# controller.net
KiCad netlist of a schematic drawn in Altium Designer
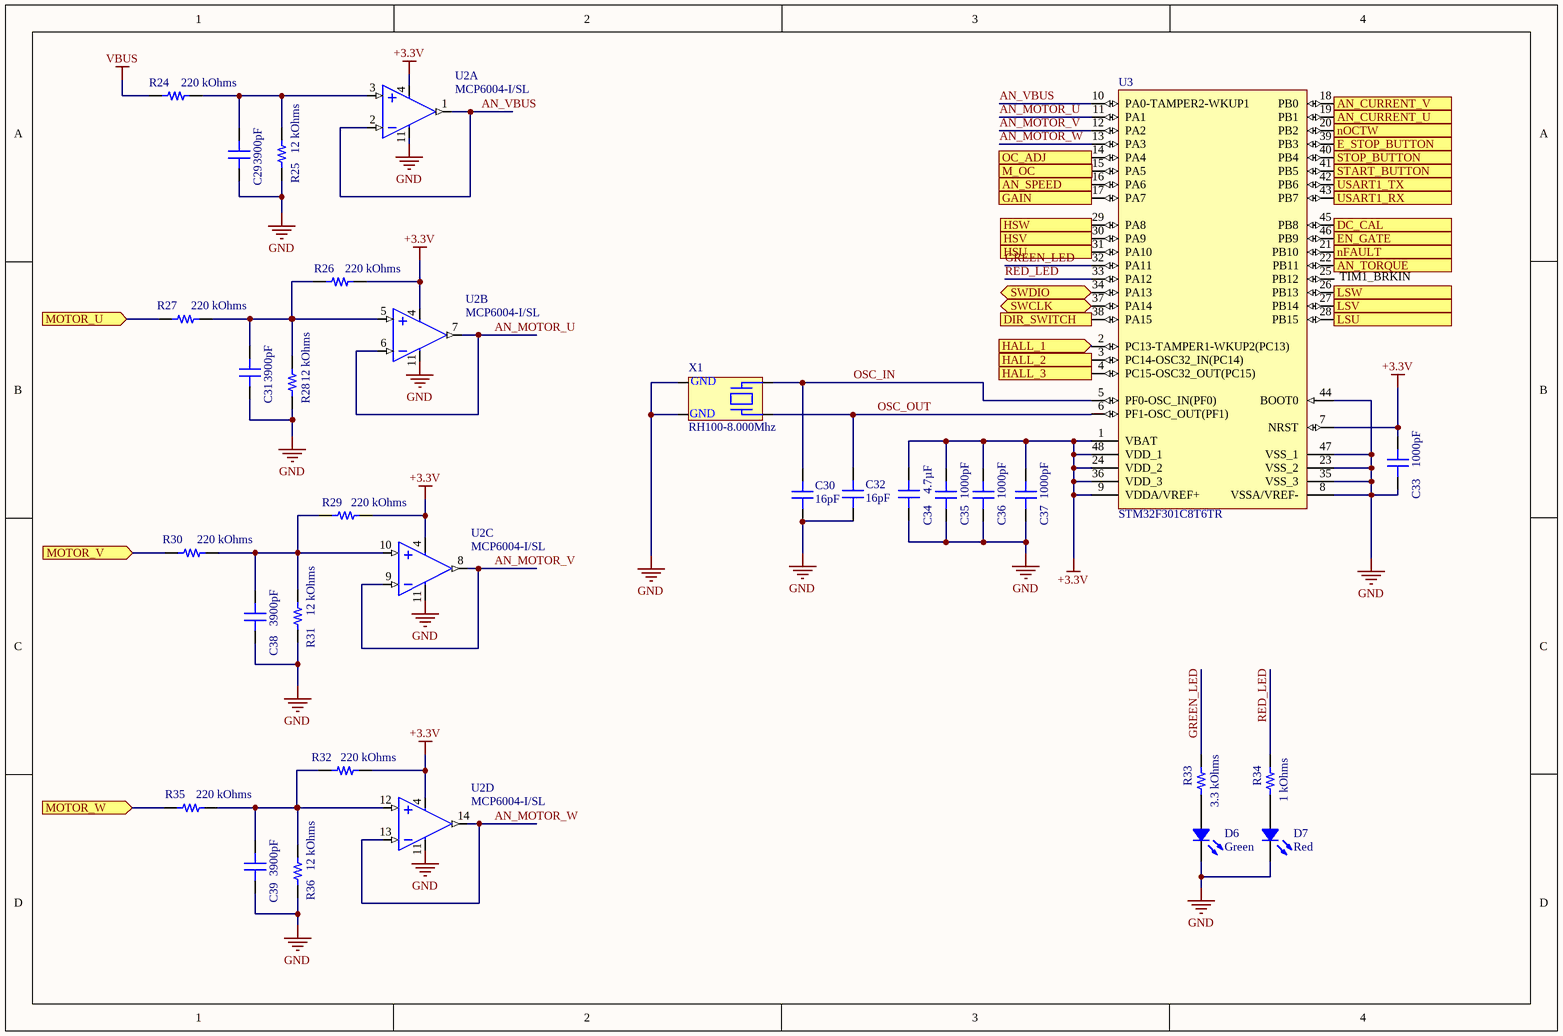
[diagram p0: controller.SchDoc]

(export (version "E")
  (design (tool "Eeschema 10.0.6"))
  (components
    (comp (ref "C29")
      (value "3900pF")
      (footprint "CAP 0402_1005")
      (description "CAP CER 3900PF 50V X7R 0402")
      (fields (field (name "PART NUMBER") "CC0402JRX7R9BB392") (field (name "MANUFACTURER") "Yageo"))
      (libsource (lib "Celestial Altium Library - altium_library") (part "Capacitor"))
    )
    (comp (ref "C30")
      (value "16pF")
      (footprint "CAP 0402_1005")
      (description "CAP CER 16PF 50V C0G/NP0 0402")
      (fields (field (name "PART NUMBER") "CBR04C160F5GAC") (field (name "MANUFACTURER") "KEMET"))
      (libsource (lib "Celestial Altium Library - altium_library") (part "Capacitor"))
    )
    (comp (ref "C31")
      (value "3900pF")
      (footprint "CAP 0402_1005")
      (description "CAP CER 3900PF 50V X7R 0402")
      (fields (field (name "PART NUMBER") "CC0402JRX7R9BB392") (field (name "MANUFACTURER") "Yageo"))
      (libsource (lib "Celestial Altium Library - altium_library") (part "Capacitor"))
    )
    (comp (ref "C32")
      (value "16pF")
      (footprint "CAP 0402_1005")
      (description "CAP CER 16PF 50V C0G/NP0 0402")
      (fields (field (name "PART NUMBER") "CBR04C160F5GAC") (field (name "MANUFACTURER") "KEMET"))
      (libsource (lib "Celestial Altium Library - altium_library") (part "Capacitor"))
    )
    (comp (ref "C33")
      (value "1000pF")
      (footprint "CAP 0402_1005")
      (description "CAP CER 1000PF 25V X7R 0402")
      (fields
        (field (name "PART NUMBER") "CGJ2B2X7R1E102K050BA")
        (field (name "MANUFACTURER") "TDK Corporation")
      )
      (libsource (lib "Celestial Altium Library - altium_library") (part "Capacitor"))
    )
    (comp (ref "C34")
      (value "4.7µF")
      (footprint "CAP 1206_3216 - 1.0MM")
      (description "CAP CER 4.7UF 25V X7R 1206")
      (fields
        (field (name "PART NUMBER") "C3216X7R1E475K085AB")
        (field (name "MANUFACTURER") "TDK Corporation")
      )
      (libsource (lib "Celestial Altium Library - altium_library") (part "Capacitor"))
    )
    (comp (ref "C35")
      (value "1000pF")
      (footprint "CAP 0402_1005")
      (description "CAP CER 1000PF 25V X7R 0402")
      (fields
        (field (name "PART NUMBER") "CGJ2B2X7R1E102K050BA")
        (field (name "MANUFACTURER") "TDK Corporation")
      )
      (libsource (lib "Celestial Altium Library - altium_library") (part "Capacitor"))
    )
    (comp (ref "C36")
      (value "1000pF")
      (footprint "CAP 0402_1005")
      (description "CAP CER 1000PF 25V X7R 0402")
      (fields
        (field (name "PART NUMBER") "CGJ2B2X7R1E102K050BA")
        (field (name "MANUFACTURER") "TDK Corporation")
      )
      (libsource (lib "Celestial Altium Library - altium_library") (part "Capacitor"))
    )
    (comp (ref "C37")
      (value "1000pF")
      (footprint "CAP 0402_1005")
      (description "CAP CER 1000PF 25V X7R 0402")
      (fields
        (field (name "PART NUMBER") "CGJ2B2X7R1E102K050BA")
        (field (name "MANUFACTURER") "TDK Corporation")
      )
      (libsource (lib "Celestial Altium Library - altium_library") (part "Capacitor"))
    )
    (comp (ref "C38")
      (value "3900pF")
      (footprint "CAP 0402_1005")
      (description "CAP CER 3900PF 50V X7R 0402")
      (fields (field (name "PART NUMBER") "CC0402JRX7R9BB392") (field (name "MANUFACTURER") "Yageo"))
      (libsource (lib "Celestial Altium Library - altium_library") (part "Capacitor"))
    )
    (comp (ref "C39")
      (value "3900pF")
      (footprint "CAP 0402_1005")
      (description "CAP CER 3900PF 50V X7R 0402")
      (fields (field (name "PART NUMBER") "CC0402JRX7R9BB392") (field (name "MANUFACTURER") "Yageo"))
      (libsource (lib "Celestial Altium Library - altium_library") (part "Capacitor"))
    )
    (comp (ref "D6")
      (value "Green")
      (footprint "LED 1206_3216 GREEN")
      (description "LED GREEN CLEAR 1206 SMD")
      (fields
        (field (name "PART NUMBER") "SML-LX1206SUGC-TR")
        (field (name "MANUFACTURER") "Lumex Opto/Components Inc.")
      )
      (libsource (lib "Celestial Altium Library - altium_library") (part "LED"))
    )
    (comp (ref "D7")
      (value "Red")
      (footprint "LED 1206_3216 RED")
      (description "LED RED CLEAR CHIP SMD")
      (fields (field (name "PART NUMBER") "AP3216SURCK") (field (name "MANUFACTURER") "Kingbright"))
      (libsource (lib "Celestial Altium Library - altium_library") (part "LED"))
    )
    (comp (ref "R24")
      (value "220 kOhms")
      (footprint "RES 1206_3216")
      (description "RES SMD 220K OHM 1% 1/4W 1206")
      (fields (field (name "PART NUMBER") "AC1206FR-07220KL") (field (name "MANUFACTURER") "Yageo"))
      (libsource (lib "Celestial Altium Library - altium_library") (part "Resistor"))
    )
    (comp (ref "R25")
      (value "12 kOhms")
      (footprint "RES 1206_3216")
      (description "RES 12K OHM 1% 1/4W 1206")
      (fields
        (field (name "PART NUMBER") "RMCF1206FT12K0")
        (field (name "MANUFACTURER") "Stackpole Electronics Inc")
      )
      (libsource (lib "Celestial Altium Library - altium_library") (part "Resistor"))
    )
    (comp (ref "R26")
      (value "220 kOhms")
      (footprint "RES 1206_3216")
      (description "RES SMD 220K OHM 1% 1/4W 1206")
      (fields (field (name "PART NUMBER") "AC1206FR-07220KL") (field (name "MANUFACTURER") "Yageo"))
      (libsource (lib "Celestial Altium Library - altium_library") (part "Resistor"))
    )
    (comp (ref "R27")
      (value "220 kOhms")
      (footprint "RES 1206_3216")
      (description "RES SMD 220K OHM 1% 1/4W 1206")
      (fields (field (name "PART NUMBER") "AC1206FR-07220KL") (field (name "MANUFACTURER") "Yageo"))
      (libsource (lib "Celestial Altium Library - altium_library") (part "Resistor"))
    )
    (comp (ref "R28")
      (value "12 kOhms")
      (footprint "RES 1206_3216")
      (description "RES 12K OHM 1% 1/4W 1206")
      (fields
        (field (name "PART NUMBER") "RMCF1206FT12K0")
        (field (name "MANUFACTURER") "Stackpole Electronics Inc")
      )
      (libsource (lib "Celestial Altium Library - altium_library") (part "Resistor"))
    )
    (comp (ref "R29")
      (value "220 kOhms")
      (footprint "RES 1206_3216")
      (description "RES SMD 220K OHM 1% 1/4W 1206")
      (fields (field (name "PART NUMBER") "AC1206FR-07220KL") (field (name "MANUFACTURER") "Yageo"))
      (libsource (lib "Celestial Altium Library - altium_library") (part "Resistor"))
    )
    (comp (ref "R30")
      (value "220 kOhms")
      (footprint "RES 1206_3216")
      (description "RES SMD 220K OHM 1% 1/4W 1206")
      (fields (field (name "PART NUMBER") "AC1206FR-07220KL") (field (name "MANUFACTURER") "Yageo"))
      (libsource (lib "Celestial Altium Library - altium_library") (part "Resistor"))
    )
    (comp (ref "R31")
      (value "12 kOhms")
      (footprint "RES 1206_3216")
      (description "RES 12K OHM 1% 1/4W 1206")
      (fields
        (field (name "PART NUMBER") "RMCF1206FT12K0")
        (field (name "MANUFACTURER") "Stackpole Electronics Inc")
      )
      (libsource (lib "Celestial Altium Library - altium_library") (part "Resistor"))
    )
    (comp (ref "R32")
      (value "220 kOhms")
      (footprint "RES 1206_3216")
      (description "RES SMD 220K OHM 1% 1/4W 1206")
      (fields (field (name "PART NUMBER") "AC1206FR-07220KL") (field (name "MANUFACTURER") "Yageo"))
      (libsource (lib "Celestial Altium Library - altium_library") (part "Resistor"))
    )
    (comp (ref "R33")
      (value "3.3 kOhms")
      (footprint "RES 1206_3216")
      (description "RES SMD 3.3K OHM 1% 1/4W 1206")
      (fields (field (name "PART NUMBER") "CRCW12063K30FKEA") (field (name "MANUFACTURER") "Vishay Dale"))
      (libsource (lib "Celestial Altium Library - altium_library") (part "Resistor"))
    )
    (comp (ref "R34")
      (value "1 kOhms")
      (footprint "RES 1206_3216")
      (description "RES SMD 1K OHM 1% 1/4W 1206")
      (fields (field (name "PART NUMBER") "RC1206FR-071KL") (field (name "MANUFACTURER") "Yageo"))
      (libsource (lib "Celestial Altium Library - altium_library") (part "Resistor"))
    )
    (comp (ref "R35")
      (value "220 kOhms")
      (footprint "RES 1206_3216")
      (description "RES SMD 220K OHM 1% 1/4W 1206")
      (fields (field (name "PART NUMBER") "AC1206FR-07220KL") (field (name "MANUFACTURER") "Yageo"))
      (libsource (lib "Celestial Altium Library - altium_library") (part "Resistor"))
    )
    (comp (ref "R36")
      (value "12 kOhms")
      (footprint "RES 1206_3216")
      (description "RES 12K OHM 1% 1/4W 1206")
      (fields
        (field (name "PART NUMBER") "RMCF1206FT12K0")
        (field (name "MANUFACTURER") "Stackpole Electronics Inc")
      )
      (libsource (lib "Celestial Altium Library - altium_library") (part "Resistor"))
    )
    (comp (ref "U2")
      (value "MCP6004-I/SL")
      (footprint "SOIC-SL14_N")
      (description "1 MHz, Low-Power Operational Amplifier, 14-Pin SOIC, Industrial Temperature")
      (libsource (lib "My_library_OpAmp") (part "MCP6004"))
    )
    (comp (ref "U3")
      (value "STM32F301C8T6TR")
      (footprint "STM-LQFP48_H")
      (libsource (lib "My_Library_MCU") (part "STM32F301C8T6"))
    )
    (comp (ref "X1")
      (value "RH100-8.000Mhz")
      (footprint "RH100-8.000")
      (libsource (lib "My_library_Oscillator") (part "RH100-8.000Mhz"))
    )
  )
  (nets
    (net (code "1") (name "+3.3V") (class "Default")
      (node (ref "C33") (pin "2") (pinfunction "2_2") (pintype "passive"))
      (node (ref "C34") (pin "2") (pinfunction "2_2") (pintype "passive"))
      (node (ref "C35") (pin "2") (pinfunction "2_2") (pintype "passive"))
      (node (ref "C36") (pin "2") (pinfunction "2_2") (pintype "passive"))
      (node (ref "C37") (pin "2") (pinfunction "2_2") (pintype "passive"))
      (node (ref "R26") (pin "1") (pinfunction "1_1") (pintype "passive"))
      (node (ref "R29") (pin "1") (pinfunction "1_1") (pintype "passive"))
      (node (ref "R32") (pin "1") (pinfunction "1_1") (pintype "passive"))
      (node (ref "U2") (pin "4") (pinfunction "VDD_4") (pintype "passive"))
      (node (ref "U3") (pin "1") (pinfunction "VBAT_1") (pintype "power_in"))
      (node (ref "U3") (pin "24") (pinfunction "VDD_2_24") (pintype "power_in"))
      (node (ref "U3") (pin "36") (pinfunction "VDD_3_36") (pintype "power_in"))
      (node (ref "U3") (pin "48") (pinfunction "VDD_1_48") (pintype "power_in"))
      (node (ref "U3") (pin "7") (pinfunction "NRST_7") (pintype "bidirectional"))
      (node (ref "U3") (pin "9") (pinfunction "VDDA/VREF+_9") (pintype "power_in"))
    )
    (net (code "2") (name "/AN_CURRENT_U") (class "Default")
      (node (ref "U3") (pin "19") (pinfunction "PB1_19") (pintype "bidirectional"))
    )
    (net (code "3") (name "/AN_CURRENT_V") (class "Default")
      (node (ref "U3") (pin "18") (pinfunction "PB0_18") (pintype "bidirectional"))
    )
    (net (code "4") (name "/AN_MOTOR_U") (class "Default")
      (node (ref "U2") (pin "6") (pinfunction "VINB-_6") (pintype "input"))
      (node (ref "U2") (pin "7") (pinfunction "VOUTB_7") (pintype "output"))
      (node (ref "U3") (pin "11") (pinfunction "PA1_11") (pintype "bidirectional"))
    )
    (net (code "5") (name "/AN_MOTOR_V") (class "Default")
      (node (ref "U2") (pin "8") (pinfunction "VOUTC_8") (pintype "output"))
      (node (ref "U2") (pin "9") (pinfunction "VINC-_9") (pintype "input"))
      (node (ref "U3") (pin "12") (pinfunction "PA2_12") (pintype "bidirectional"))
    )
    (net (code "6") (name "/AN_MOTOR_W") (class "Default")
      (node (ref "U2") (pin "13") (pinfunction "VIND-_13") (pintype "input"))
      (node (ref "U2") (pin "14") (pinfunction "VOUTD_14") (pintype "output"))
      (node (ref "U3") (pin "13") (pinfunction "PA3_13") (pintype "bidirectional"))
    )
    (net (code "7") (name "/AN_SPEED") (class "Default")
      (node (ref "U3") (pin "16") (pinfunction "PA6_16") (pintype "bidirectional"))
    )
    (net (code "8") (name "/AN_TORQUE") (class "Default")
      (node (ref "U3") (pin "22") (pinfunction "PB11_22") (pintype "bidirectional"))
    )
    (net (code "9") (name "/AN_VBUS") (class "Default")
      (node (ref "U2") (pin "1") (pinfunction "VOUTA_1") (pintype "output"))
      (node (ref "U2") (pin "2") (pinfunction "VINA-_2") (pintype "input"))
      (node (ref "U3") (pin "10") (pinfunction "PA0-TAMPER2-WKUP1_10") (pintype "bidirectional"))
    )
    (net (code "10") (name "/DC_CAL") (class "Default")
      (node (ref "U3") (pin "45") (pinfunction "PB8_45") (pintype "bidirectional"))
    )
    (net (code "11") (name "/DIR_SWITCH") (class "Default")
      (node (ref "U3") (pin "38") (pinfunction "PA15_38") (pintype "bidirectional"))
    )
    (net (code "12") (name "/EN_GATE") (class "Default")
      (node (ref "U3") (pin "46") (pinfunction "PB9_46") (pintype "bidirectional"))
    )
    (net (code "13") (name "/E_STOP_BUTTON") (class "Default")
      (node (ref "U3") (pin "39") (pinfunction "PB3_39") (pintype "bidirectional"))
    )
    (net (code "14") (name "/GAIN") (class "Default")
      (node (ref "U3") (pin "17") (pinfunction "PA7_17") (pintype "bidirectional"))
    )
    (net (code "15") (name "/GREEN_LED") (class "Default")
      (node (ref "R33") (pin "2") (pinfunction "2_2") (pintype "passive"))
      (node (ref "U3") (pin "32") (pinfunction "PA11_32") (pintype "bidirectional"))
    )
    (net (code "16") (name "/HALL_1") (class "Default")
      (node (ref "U3") (pin "2") (pinfunction "PC13-TAMPER1-WKUP2(PC13)_2") (pintype "bidirectional"))
    )
    (net (code "17") (name "/HALL_2") (class "Default")
      (node (ref "U3") (pin "3") (pinfunction "PC14-OSC32_IN(PC14)_3") (pintype "bidirectional"))
    )
    (net (code "18") (name "/HALL_3") (class "Default")
      (node (ref "U3") (pin "4") (pinfunction "PC15-OSC32_OUT(PC15)_4") (pintype "bidirectional"))
    )
    (net (code "19") (name "/HSU") (class "Default")
      (node (ref "U3") (pin "31") (pinfunction "PA10_31") (pintype "bidirectional"))
    )
    (net (code "20") (name "/HSV") (class "Default")
      (node (ref "U3") (pin "30") (pinfunction "PA9_30") (pintype "bidirectional"))
    )
    (net (code "21") (name "/HSW") (class "Default")
      (node (ref "U3") (pin "29") (pinfunction "PA8_29") (pintype "bidirectional"))
    )
    (net (code "22") (name "/LSU") (class "Default")
      (node (ref "U3") (pin "28") (pinfunction "PB15_28") (pintype "bidirectional"))
    )
    (net (code "23") (name "/LSV") (class "Default")
      (node (ref "U3") (pin "27") (pinfunction "PB14_27") (pintype "bidirectional"))
    )
    (net (code "24") (name "/LSW") (class "Default")
      (node (ref "U3") (pin "26") (pinfunction "PB13_26") (pintype "bidirectional"))
    )
    (net (code "25") (name "/MOTOR_U") (class "Default")
      (node (ref "R27") (pin "2") (pinfunction "2_2") (pintype "passive"))
    )
    (net (code "26") (name "/MOTOR_V") (class "Default")
      (node (ref "R30") (pin "2") (pinfunction "2_2") (pintype "passive"))
    )
    (net (code "27") (name "/MOTOR_W") (class "Default")
      (node (ref "R35") (pin "2") (pinfunction "2_2") (pintype "passive"))
    )
    (net (code "28") (name "/M_OC") (class "Default")
      (node (ref "U3") (pin "15") (pinfunction "PA5_15") (pintype "bidirectional"))
    )
    (net (code "29") (name "/OC_ADJ") (class "Default")
      (node (ref "U3") (pin "14") (pinfunction "PA4_14") (pintype "bidirectional"))
    )
    (net (code "30") (name "/OSC_IN") (class "Default")
      (node (ref "C30") (pin "1") (pinfunction "1_1") (pintype "passive"))
      (node (ref "U3") (pin "5") (pinfunction "PF0-OSC_IN(PF0)_5") (pintype "bidirectional"))
      (node (ref "X1") (pin "4") (pinfunction "X1_4") (pintype "passive"))
    )
    (net (code "31") (name "/OSC_OUT") (class "Default")
      (node (ref "C32") (pin "1") (pinfunction "1_1") (pintype "passive"))
      (node (ref "U3") (pin "6") (pinfunction "PF1-OSC_OUT(PF1)_6") (pintype "bidirectional"))
      (node (ref "X1") (pin "2") (pinfunction "X2_2") (pintype "passive"))
    )
    (net (code "32") (name "/RED_LED") (class "Default")
      (node (ref "R34") (pin "2") (pinfunction "2_2") (pintype "passive"))
      (node (ref "U3") (pin "33") (pinfunction "PA12_33") (pintype "bidirectional"))
    )
    (net (code "33") (name "/START_BUTTON") (class "Default")
      (node (ref "U3") (pin "41") (pinfunction "PB5_41") (pintype "bidirectional"))
    )
    (net (code "34") (name "/STOP_BUTTON") (class "Default")
      (node (ref "U3") (pin "40") (pinfunction "PB4_40") (pintype "bidirectional"))
    )
    (net (code "35") (name "/SWCLK") (class "Default")
      (node (ref "U3") (pin "37") (pinfunction "PA14_37") (pintype "bidirectional"))
    )
    (net (code "36") (name "/SWDIO") (class "Default")
      (node (ref "U3") (pin "34") (pinfunction "PA13_34") (pintype "bidirectional"))
    )
    (net (code "37") (name "/USART1_RX") (class "Default")
      (node (ref "U3") (pin "43") (pinfunction "PB7_43") (pintype "bidirectional"))
    )
    (net (code "38") (name "/USART1_TX") (class "Default")
      (node (ref "U3") (pin "42") (pinfunction "PB6_42") (pintype "bidirectional"))
    )
    (net (code "39") (name "/nFAULT") (class "Default")
      (node (ref "U3") (pin "21") (pinfunction "PB10_21") (pintype "bidirectional"))
    )
    (net (code "40") (name "/nOCTW") (class "Default")
      (node (ref "U3") (pin "20") (pinfunction "PB2_20") (pintype "bidirectional"))
    )
    (net (code "41") (name "GND") (class "Default")
      (node (ref "C29") (pin "1") (pinfunction "1_1") (pintype "passive"))
      (node (ref "C30") (pin "2") (pinfunction "2_2") (pintype "passive"))
      (node (ref "C31") (pin "1") (pinfunction "1_1") (pintype "passive"))
      (node (ref "C32") (pin "2") (pinfunction "2_2") (pintype "passive"))
      (node (ref "C33") (pin "1") (pinfunction "1_1") (pintype "passive"))
      (node (ref "C34") (pin "1") (pinfunction "1_1") (pintype "passive"))
      (node (ref "C35") (pin "1") (pinfunction "1_1") (pintype "passive"))
      (node (ref "C36") (pin "1") (pinfunction "1_1") (pintype "passive"))
      (node (ref "C37") (pin "1") (pinfunction "1_1") (pintype "passive"))
      (node (ref "C38") (pin "1") (pinfunction "1_1") (pintype "passive"))
      (node (ref "C39") (pin "1") (pinfunction "1_1") (pintype "passive"))
      (node (ref "D6") (pin "2") (pinfunction "2_2") (pintype "passive"))
      (node (ref "D7") (pin "2") (pinfunction "2_2") (pintype "passive"))
      (node (ref "R25") (pin "1") (pinfunction "1_1") (pintype "passive"))
      (node (ref "R28") (pin "1") (pinfunction "1_1") (pintype "passive"))
      (node (ref "R31") (pin "1") (pinfunction "1_1") (pintype "passive"))
      (node (ref "R36") (pin "1") (pinfunction "1_1") (pintype "passive"))
      (node (ref "U2") (pin "11") (pinfunction "VSS_11") (pintype "power_in"))
      (node (ref "U3") (pin "23") (pinfunction "VSS_2_23") (pintype "power_in"))
      (node (ref "U3") (pin "35") (pinfunction "VSS_3_35") (pintype "power_in"))
      (node (ref "U3") (pin "44") (pinfunction "BOOT0_44") (pintype "input"))
      (node (ref "U3") (pin "47") (pinfunction "VSS_1_47") (pintype "power_in"))
      (node (ref "U3") (pin "8") (pinfunction "VSSA/VREF-_8") (pintype "power_in"))
      (node (ref "X1") (pin "1") (pinfunction "GND_1") (pintype "passive"))
      (node (ref "X1") (pin "3") (pinfunction "GND_3") (pintype "passive"))
    )
    (net (code "42") (name "Net-(D6-Pad1)") (class "Default")
      (node (ref "D6") (pin "1") (pinfunction "1_1") (pintype "passive"))
      (node (ref "R33") (pin "1") (pinfunction "1_1") (pintype "passive"))
    )
    (net (code "43") (name "Net-(D7-Pad1)") (class "Default")
      (node (ref "D7") (pin "1") (pinfunction "1_1") (pintype "passive"))
      (node (ref "R34") (pin "1") (pinfunction "1_1") (pintype "passive"))
    )
    (net (code "44") (name "Net-(U2A-VINA+)") (class "Default")
      (node (ref "C29") (pin "2") (pinfunction "2_2") (pintype "passive"))
      (node (ref "R24") (pin "1") (pinfunction "1_1") (pintype "passive"))
      (node (ref "R25") (pin "2") (pinfunction "2_2") (pintype "passive"))
      (node (ref "U2") (pin "3") (pinfunction "VINA+_3") (pintype "input"))
    )
    (net (code "45") (name "Net-(U2B-VINB+)") (class "Default")
      (node (ref "C31") (pin "2") (pinfunction "2_2") (pintype "passive"))
      (node (ref "R26") (pin "2") (pinfunction "2_2") (pintype "passive"))
      (node (ref "R27") (pin "1") (pinfunction "1_1") (pintype "passive"))
      (node (ref "R28") (pin "2") (pinfunction "2_2") (pintype "passive"))
      (node (ref "U2") (pin "5") (pinfunction "VINB+_5") (pintype "input"))
    )
    (net (code "46") (name "Net-(U2C-VINC+)") (class "Default")
      (node (ref "C38") (pin "2") (pinfunction "2_2") (pintype "passive"))
      (node (ref "R29") (pin "2") (pinfunction "2_2") (pintype "passive"))
      (node (ref "R30") (pin "1") (pinfunction "1_1") (pintype "passive"))
      (node (ref "R31") (pin "2") (pinfunction "2_2") (pintype "passive"))
      (node (ref "U2") (pin "10") (pinfunction "VINC+_10") (pintype "input"))
    )
    (net (code "47") (name "Net-(U2D-VIND+)") (class "Default")
      (node (ref "C39") (pin "2") (pinfunction "2_2") (pintype "passive"))
      (node (ref "R32") (pin "2") (pinfunction "2_2") (pintype "passive"))
      (node (ref "R35") (pin "1") (pinfunction "1_1") (pintype "passive"))
      (node (ref "R36") (pin "2") (pinfunction "2_2") (pintype "passive"))
      (node (ref "U2") (pin "12") (pinfunction "VIND+_12") (pintype "input"))
    )
    (net (code "48") (name "VBUS") (class "Default")
      (node (ref "R24") (pin "2") (pinfunction "2_2") (pintype "passive"))
    )
    (net (code "49") (name "unconnected-(U3-PB12-Pad25)") (class "Default")
      (node (ref "U3") (pin "25") (pinfunction "PB12_25") (pintype "bidirectional"))
    )
  )
)
